# Interface.net
KiCad netlist of a schematic drawn in EAGLE
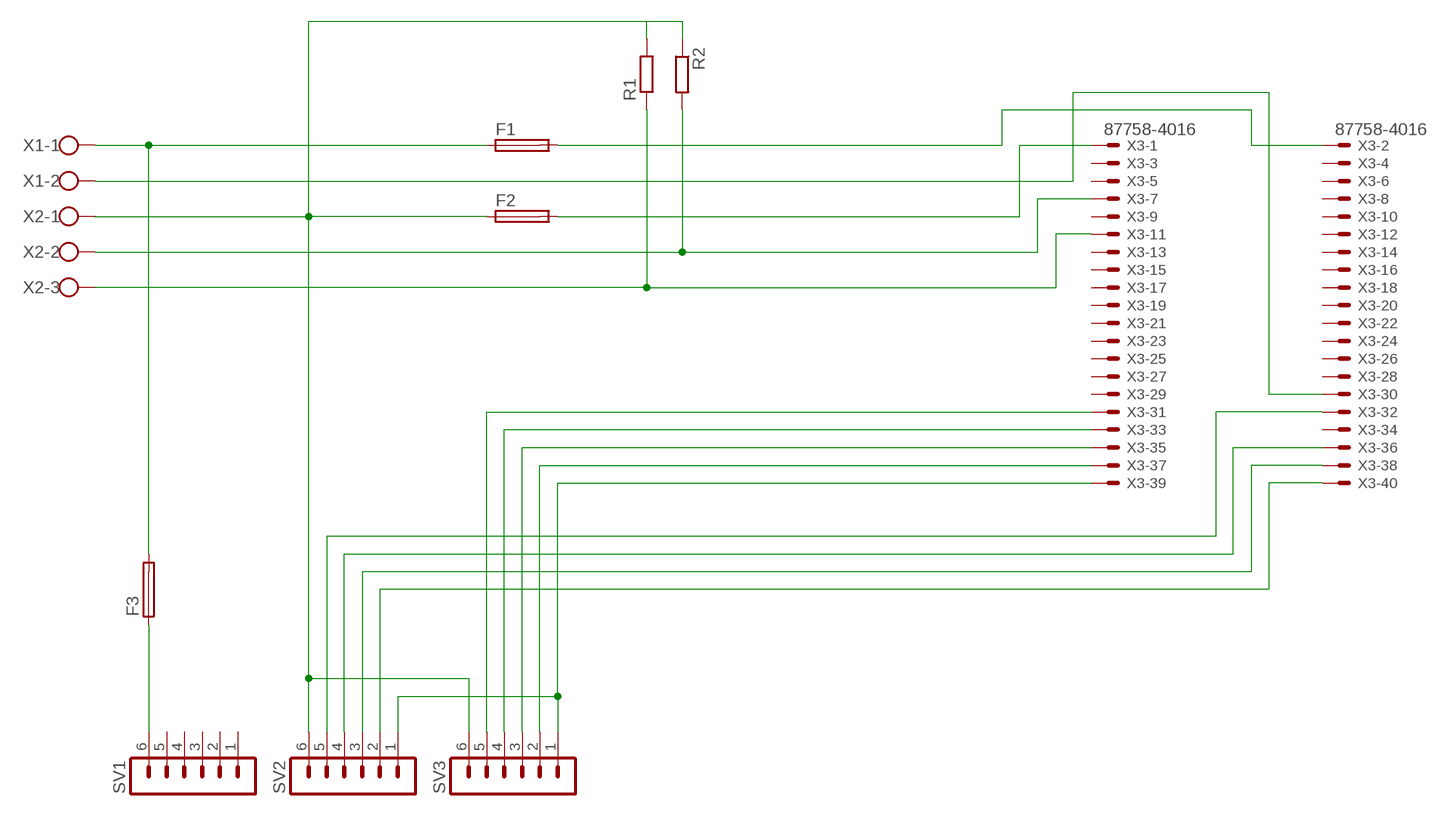
[diagram p0: schematic, sheet 1]

(export (version "E")
  (design (tool "Eeschema 10.0.6"))
  (components
    (comp (ref "F1")
      (value "GSH15")
      (footprint "eagle-import:GSH15")
      (fields (field (name "MPN") "64900001039"))
      (libsource (lib "eagle-import") (part "GSH15"))
    )
    (comp (ref "F2")
      (value "GSH15")
      (footprint "eagle-import:GSH15")
      (fields (field (name "MPN") "64900001039"))
      (libsource (lib "eagle-import") (part "GSH15"))
    )
    (comp (ref "F3")
      (value "GSH15")
      (footprint "eagle-import:GSH15")
      (fields (field (name "MPN") "64900001039"))
      (libsource (lib "eagle-import") (part "GSH15"))
    )
    (comp (ref "R1")
      (value "R-EU_0207/10")
      (footprint "eagle-import:0207_10")
      (libsource (lib "eagle-import") (part "R-EU_0207/10"))
    )
    (comp (ref "R2")
      (value "R-EU_0207/5V")
      (footprint "eagle-import:0207_5V")
      (libsource (lib "eagle-import") (part "R-EU_0207/5V"))
    )
    (comp (ref "SV1")
      (value "MA06-1")
      (footprint "eagle-import:MA06-1")
      (libsource (lib "eagle-import") (part "MA06-1"))
    )
    (comp (ref "SV2")
      (value "MA06-1")
      (footprint "eagle-import:MA06-1")
      (libsource (lib "eagle-import") (part "MA06-1"))
    )
    (comp (ref "SV3")
      (value "MA06-1")
      (footprint "eagle-import:MA06-1")
      (libsource (lib "eagle-import") (part "MA06-1"))
    )
    (comp (ref "X1")
      (value "W237-102")
      (footprint "eagle-import:W237-102")
      (fields (field (name "MPN") "237-102"))
      (libsource (lib "eagle-import") (part "W237-102"))
    )
    (comp (ref "X2")
      (value "W237-103")
      (footprint "eagle-import:W237-103")
      (fields (field (name "MPN") "237-103"))
      (libsource (lib "eagle-import") (part "W237-103"))
    )
    (comp (ref "X3")
      (value "87758-4016")
      (footprint "eagle-import:87758-4016")
      (libsource (lib "eagle-import") (part "87758-4016"))
    )
  )
  (nets
    (net (code "1") (name "Net-(F3-Pad1)") (class "Default")
      (node (ref "F3") (pin "1") (pinfunction "1_1") (pintype "passive"))
      (node (ref "SV1") (pin "6") (pinfunction "6_6") (pintype "passive"))
    )
    (net (code "2") (name "Net-(X1A-KL)") (class "Default")
      (node (ref "F1") (pin "1") (pinfunction "1_1") (pintype "passive"))
      (node (ref "F3") (pin "2") (pinfunction "2_2") (pintype "passive"))
      (node (ref "X1") (pin "1") (pinfunction "KL_1") (pintype "passive"))
    )
    (net (code "3") (name "Net-(X1B-KL)") (class "Default")
      (node (ref "X1") (pin "2") (pinfunction "KL_2") (pintype "passive"))
      (node (ref "X3") (pin "30") (pinfunction "S_30") (pintype "passive"))
    )
    (net (code "4") (name "Net-(X2A-KL)") (class "Default")
      (node (ref "F2") (pin "1") (pinfunction "1_1") (pintype "passive"))
      (node (ref "R1") (pin "2") (pinfunction "2_2") (pintype "passive"))
      (node (ref "R2") (pin "1") (pinfunction "1_1") (pintype "passive"))
      (node (ref "SV2") (pin "6") (pinfunction "6_6") (pintype "passive"))
      (node (ref "SV3") (pin "6") (pinfunction "6_6") (pintype "passive"))
      (node (ref "X2") (pin "1") (pinfunction "KL_1") (pintype "passive"))
    )
    (net (code "5") (name "Net-(X2B-KL)") (class "Default")
      (node (ref "R2") (pin "2") (pinfunction "2_2") (pintype "passive"))
      (node (ref "X2") (pin "2") (pinfunction "KL_2") (pintype "passive"))
      (node (ref "X3") (pin "7") (pinfunction "S_7") (pintype "passive"))
    )
    (net (code "6") (name "Net-(X2C-KL)") (class "Default")
      (node (ref "R1") (pin "1") (pinfunction "1_1") (pintype "passive"))
      (node (ref "X2") (pin "3") (pinfunction "KL_3") (pintype "passive"))
      (node (ref "X3") (pin "11") (pinfunction "S_11") (pintype "passive"))
    )
    (net (code "7") (name "Net-(X3A-S)") (class "Default")
      (node (ref "F2") (pin "2") (pinfunction "2_2") (pintype "passive"))
      (node (ref "X3") (pin "1") (pinfunction "S_1") (pintype "passive"))
    )
    (net (code "8") (name "Net-(X3AA-S)") (class "Default")
      (node (ref "SV3") (pin "4") (pinfunction "4_4") (pintype "passive"))
      (node (ref "X3") (pin "33") (pinfunction "S_33") (pintype "passive"))
    )
    (net (code "9") (name "Net-(X3AC-S)") (class "Default")
      (node (ref "SV3") (pin "3") (pinfunction "3_3") (pintype "passive"))
      (node (ref "X3") (pin "35") (pinfunction "S_35") (pintype "passive"))
    )
    (net (code "10") (name "Net-(X3AD-S)") (class "Default")
      (node (ref "SV2") (pin "4") (pinfunction "4_4") (pintype "passive"))
      (node (ref "X3") (pin "36") (pinfunction "S_36") (pintype "passive"))
    )
    (net (code "11") (name "Net-(X3AE-S)") (class "Default")
      (node (ref "SV3") (pin "2") (pinfunction "2_2") (pintype "passive"))
      (node (ref "X3") (pin "37") (pinfunction "S_37") (pintype "passive"))
    )
    (net (code "12") (name "Net-(X3AF-S)") (class "Default")
      (node (ref "SV2") (pin "3") (pinfunction "3_3") (pintype "passive"))
      (node (ref "X3") (pin "38") (pinfunction "S_38") (pintype "passive"))
    )
    (net (code "13") (name "Net-(X3AG-S)") (class "Default")
      (node (ref "SV2") (pin "1") (pinfunction "1_1") (pintype "passive"))
      (node (ref "SV3") (pin "1") (pinfunction "1_1") (pintype "passive"))
      (node (ref "X3") (pin "39") (pinfunction "S_39") (pintype "passive"))
    )
    (net (code "14") (name "Net-(X3AI-S)") (class "Default")
      (node (ref "SV2") (pin "2") (pinfunction "2_2") (pintype "passive"))
      (node (ref "X3") (pin "40") (pinfunction "S_40") (pintype "passive"))
    )
    (net (code "15") (name "Net-(X3L-S)") (class "Default")
      (node (ref "F1") (pin "2") (pinfunction "2_2") (pintype "passive"))
      (node (ref "X3") (pin "2") (pinfunction "S_2") (pintype "passive"))
    )
    (net (code "16") (name "Net-(X3Y-S)") (class "Default")
      (node (ref "SV3") (pin "5") (pinfunction "5_5") (pintype "passive"))
      (node (ref "X3") (pin "31") (pinfunction "S_31") (pintype "passive"))
    )
    (net (code "17") (name "Net-(X3Z-S)") (class "Default")
      (node (ref "SV2") (pin "5") (pinfunction "5_5") (pintype "passive"))
      (node (ref "X3") (pin "32") (pinfunction "S_32") (pintype "passive"))
    )
    (net (code "18") (name "unconnected-(SV1-Pad1)") (class "Default")
      (node (ref "SV1") (pin "1") (pinfunction "1_1") (pintype "passive"))
    )
    (net (code "19") (name "unconnected-(SV1-Pad2)") (class "Default")
      (node (ref "SV1") (pin "2") (pinfunction "2_2") (pintype "passive"))
    )
    (net (code "20") (name "unconnected-(SV1-Pad3)") (class "Default")
      (node (ref "SV1") (pin "3") (pinfunction "3_3") (pintype "passive"))
    )
    (net (code "21") (name "unconnected-(SV1-Pad4)") (class "Default")
      (node (ref "SV1") (pin "4") (pinfunction "4_4") (pintype "passive"))
    )
    (net (code "22") (name "unconnected-(SV1-Pad5)") (class "Default")
      (node (ref "SV1") (pin "5") (pinfunction "5_5") (pintype "passive"))
    )
    (net (code "23") (name "unconnected-(X3AB-S-Pad34)") (class "Default")
      (node (ref "X3") (pin "34") (pinfunction "S_34") (pintype "passive"))
    )
    (net (code "24") (name "unconnected-(X3AH-S-Pad4)") (class "Default")
      (node (ref "X3") (pin "4") (pinfunction "S_4") (pintype "passive"))
    )
    (net (code "25") (name "unconnected-(X3AJ-S-Pad5)") (class "Default")
      (node (ref "X3") (pin "5") (pinfunction "S_5") (pintype "passive"))
    )
    (net (code "26") (name "unconnected-(X3AK-S-Pad6)") (class "Default")
      (node (ref "X3") (pin "6") (pinfunction "S_6") (pintype "passive"))
    )
    (net (code "27") (name "unconnected-(X3AM-S-Pad8)") (class "Default")
      (node (ref "X3") (pin "8") (pinfunction "S_8") (pintype "passive"))
    )
    (net (code "28") (name "unconnected-(X3AN-S-Pad9)") (class "Default")
      (node (ref "X3") (pin "9") (pinfunction "S_9") (pintype "passive"))
    )
    (net (code "29") (name "unconnected-(X3B-S-Pad10)") (class "Default")
      (node (ref "X3") (pin "10") (pinfunction "S_10") (pintype "passive"))
    )
    (net (code "30") (name "unconnected-(X3D-S-Pad12)") (class "Default")
      (node (ref "X3") (pin "12") (pinfunction "S_12") (pintype "passive"))
    )
    (net (code "31") (name "unconnected-(X3E-S-Pad13)") (class "Default")
      (node (ref "X3") (pin "13") (pinfunction "S_13") (pintype "passive"))
    )
    (net (code "32") (name "unconnected-(X3F-S-Pad14)") (class "Default")
      (node (ref "X3") (pin "14") (pinfunction "S_14") (pintype "passive"))
    )
    (net (code "33") (name "unconnected-(X3G-S-Pad15)") (class "Default")
      (node (ref "X3") (pin "15") (pinfunction "S_15") (pintype "passive"))
    )
    (net (code "34") (name "unconnected-(X3H-S-Pad16)") (class "Default")
      (node (ref "X3") (pin "16") (pinfunction "S_16") (pintype "passive"))
    )
    (net (code "35") (name "unconnected-(X3I-S-Pad17)") (class "Default")
      (node (ref "X3") (pin "17") (pinfunction "S_17") (pintype "passive"))
    )
    (net (code "36") (name "unconnected-(X3J-S-Pad18)") (class "Default")
      (node (ref "X3") (pin "18") (pinfunction "S_18") (pintype "passive"))
    )
    (net (code "37") (name "unconnected-(X3K-S-Pad19)") (class "Default")
      (node (ref "X3") (pin "19") (pinfunction "S_19") (pintype "passive"))
    )
    (net (code "38") (name "unconnected-(X3M-S-Pad20)") (class "Default")
      (node (ref "X3") (pin "20") (pinfunction "S_20") (pintype "passive"))
    )
    (net (code "39") (name "unconnected-(X3N-S-Pad21)") (class "Default")
      (node (ref "X3") (pin "21") (pinfunction "S_21") (pintype "passive"))
    )
    (net (code "40") (name "unconnected-(X3O-S-Pad22)") (class "Default")
      (node (ref "X3") (pin "22") (pinfunction "S_22") (pintype "passive"))
    )
    (net (code "41") (name "unconnected-(X3P-S-Pad23)") (class "Default")
      (node (ref "X3") (pin "23") (pinfunction "S_23") (pintype "passive"))
    )
    (net (code "42") (name "unconnected-(X3Q-S-Pad24)") (class "Default")
      (node (ref "X3") (pin "24") (pinfunction "S_24") (pintype "passive"))
    )
    (net (code "43") (name "unconnected-(X3R-S-Pad25)") (class "Default")
      (node (ref "X3") (pin "25") (pinfunction "S_25") (pintype "passive"))
    )
    (net (code "44") (name "unconnected-(X3S-S-Pad26)") (class "Default")
      (node (ref "X3") (pin "26") (pinfunction "S_26") (pintype "passive"))
    )
    (net (code "45") (name "unconnected-(X3T-S-Pad27)") (class "Default")
      (node (ref "X3") (pin "27") (pinfunction "S_27") (pintype "passive"))
    )
    (net (code "46") (name "unconnected-(X3U-S-Pad28)") (class "Default")
      (node (ref "X3") (pin "28") (pinfunction "S_28") (pintype "passive"))
    )
    (net (code "47") (name "unconnected-(X3V-S-Pad29)") (class "Default")
      (node (ref "X3") (pin "29") (pinfunction "S_29") (pintype "passive"))
    )
    (net (code "48") (name "unconnected-(X3W-S-Pad3)") (class "Default")
      (node (ref "X3") (pin "3") (pinfunction "S_3") (pintype "passive"))
    )
  )
)
